# MemoryExpansion.net
KiCad netlist of a schematic drawn in EAGLE
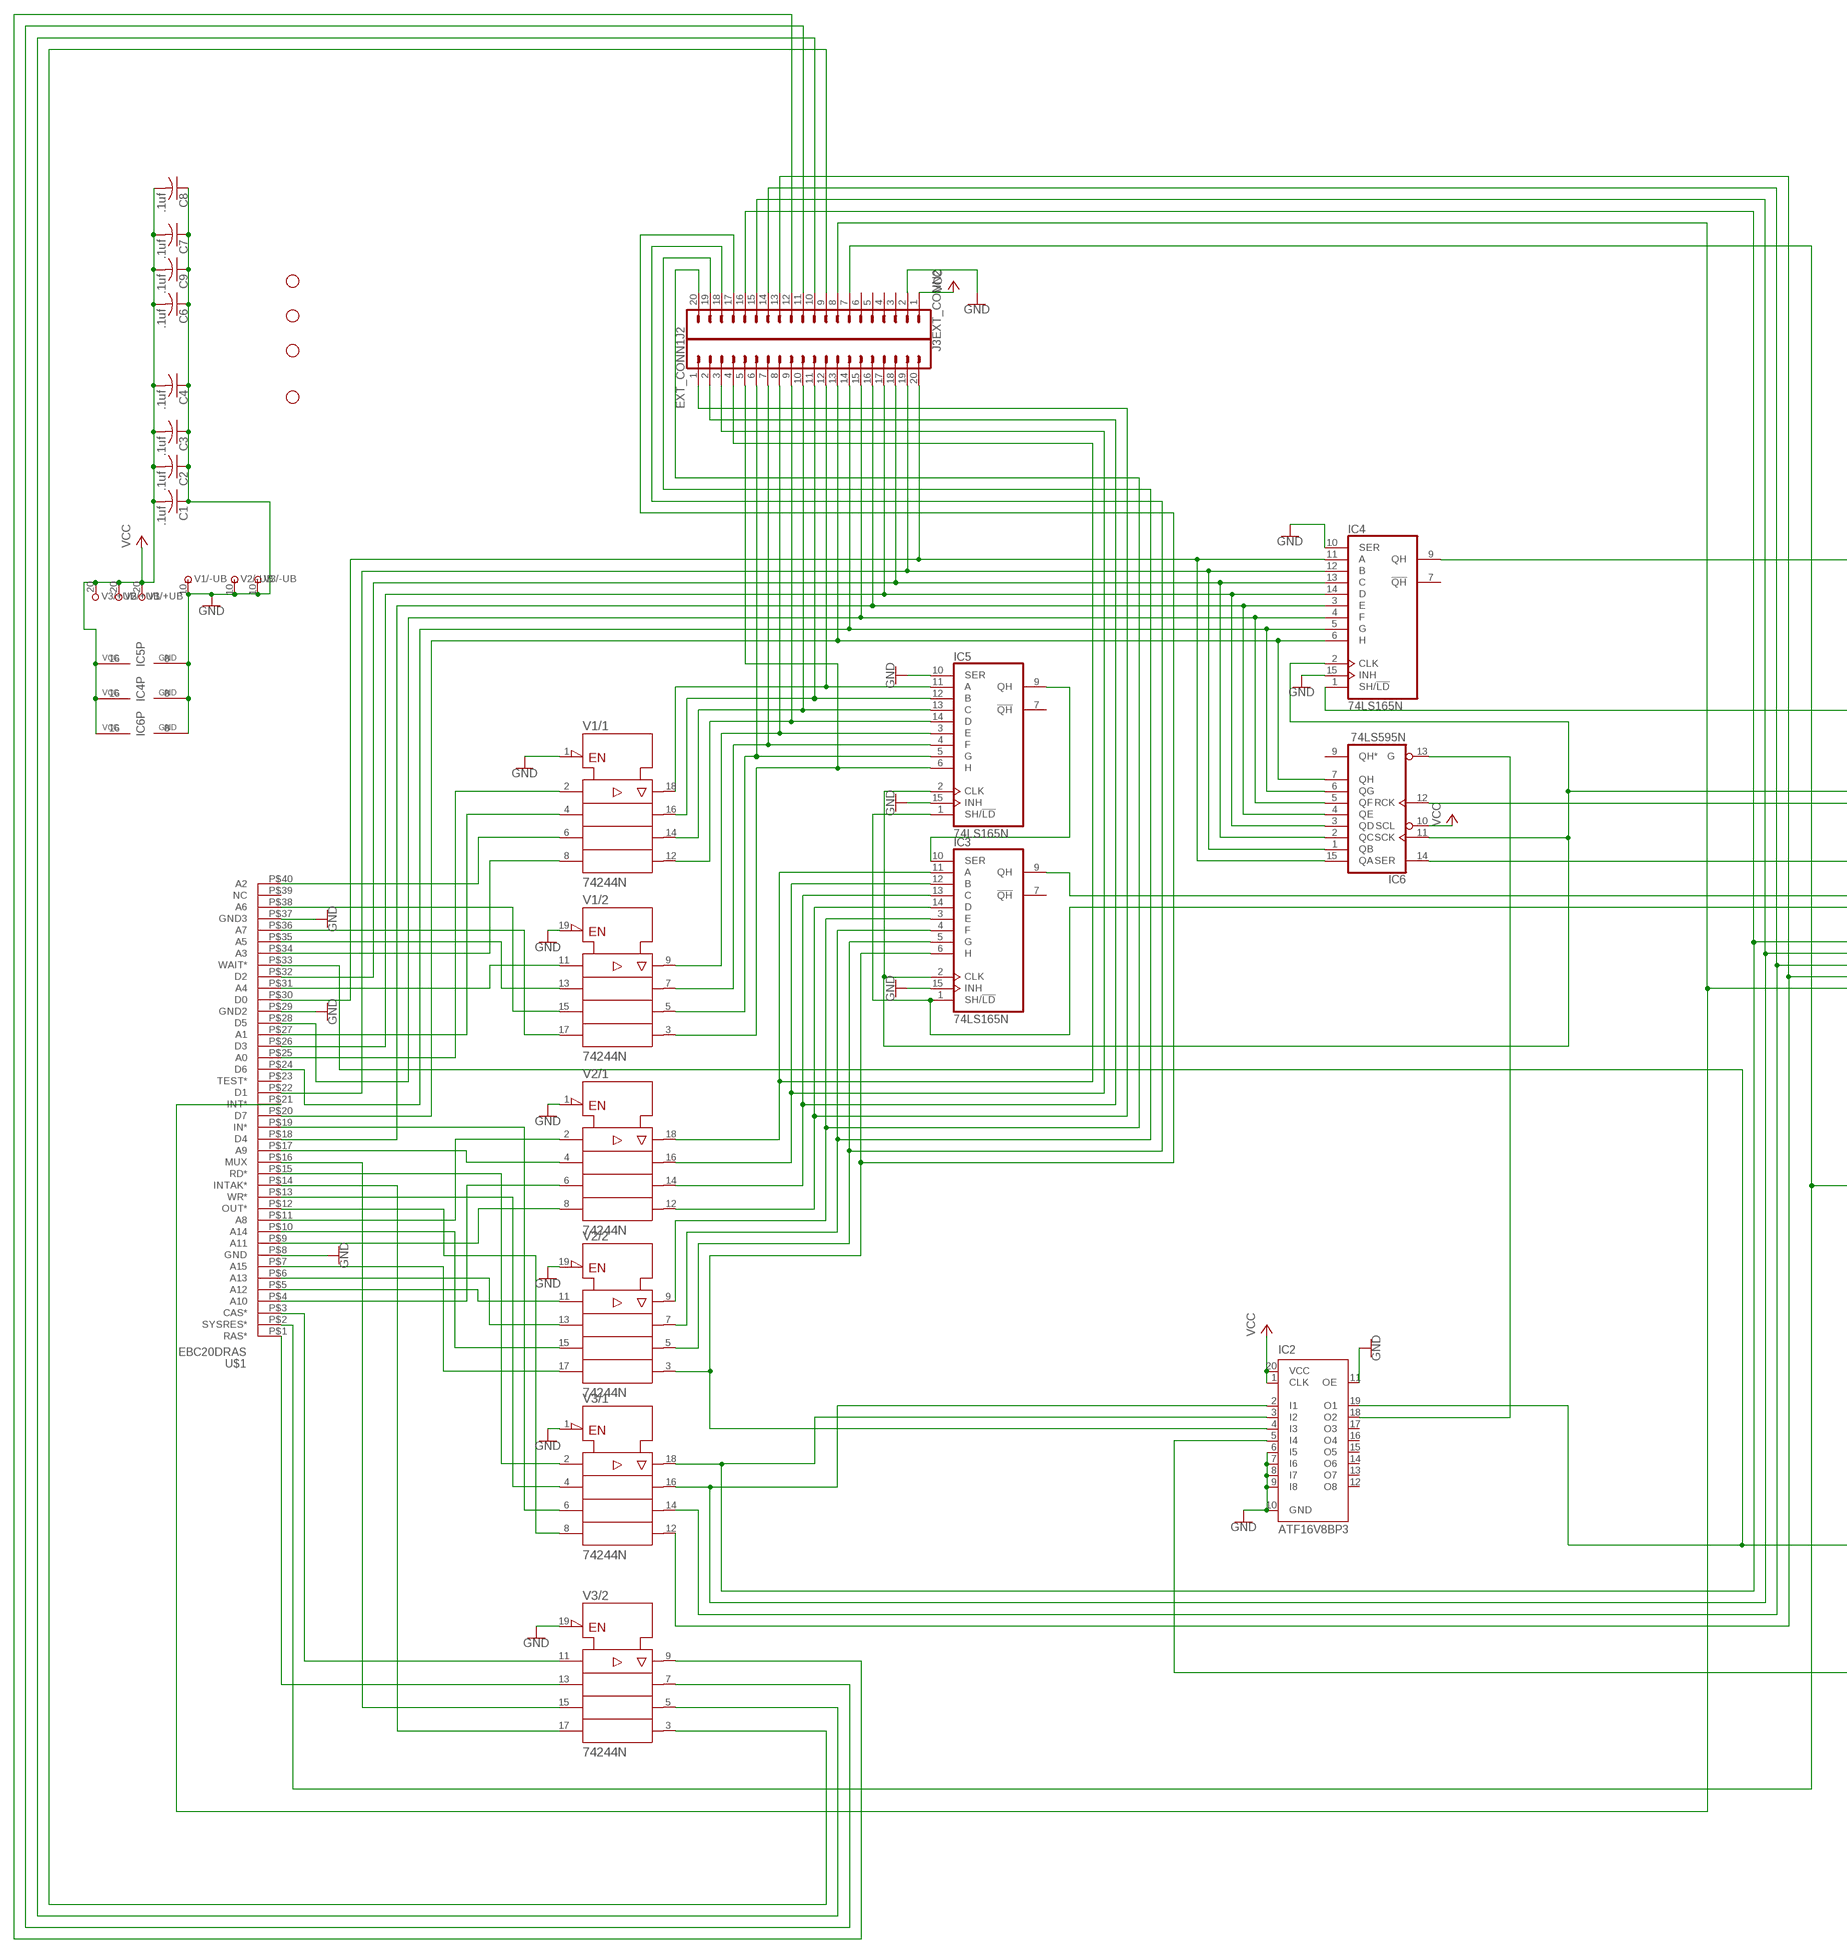
[diagram p0: schematic, sheet 1, part 1 of 2]
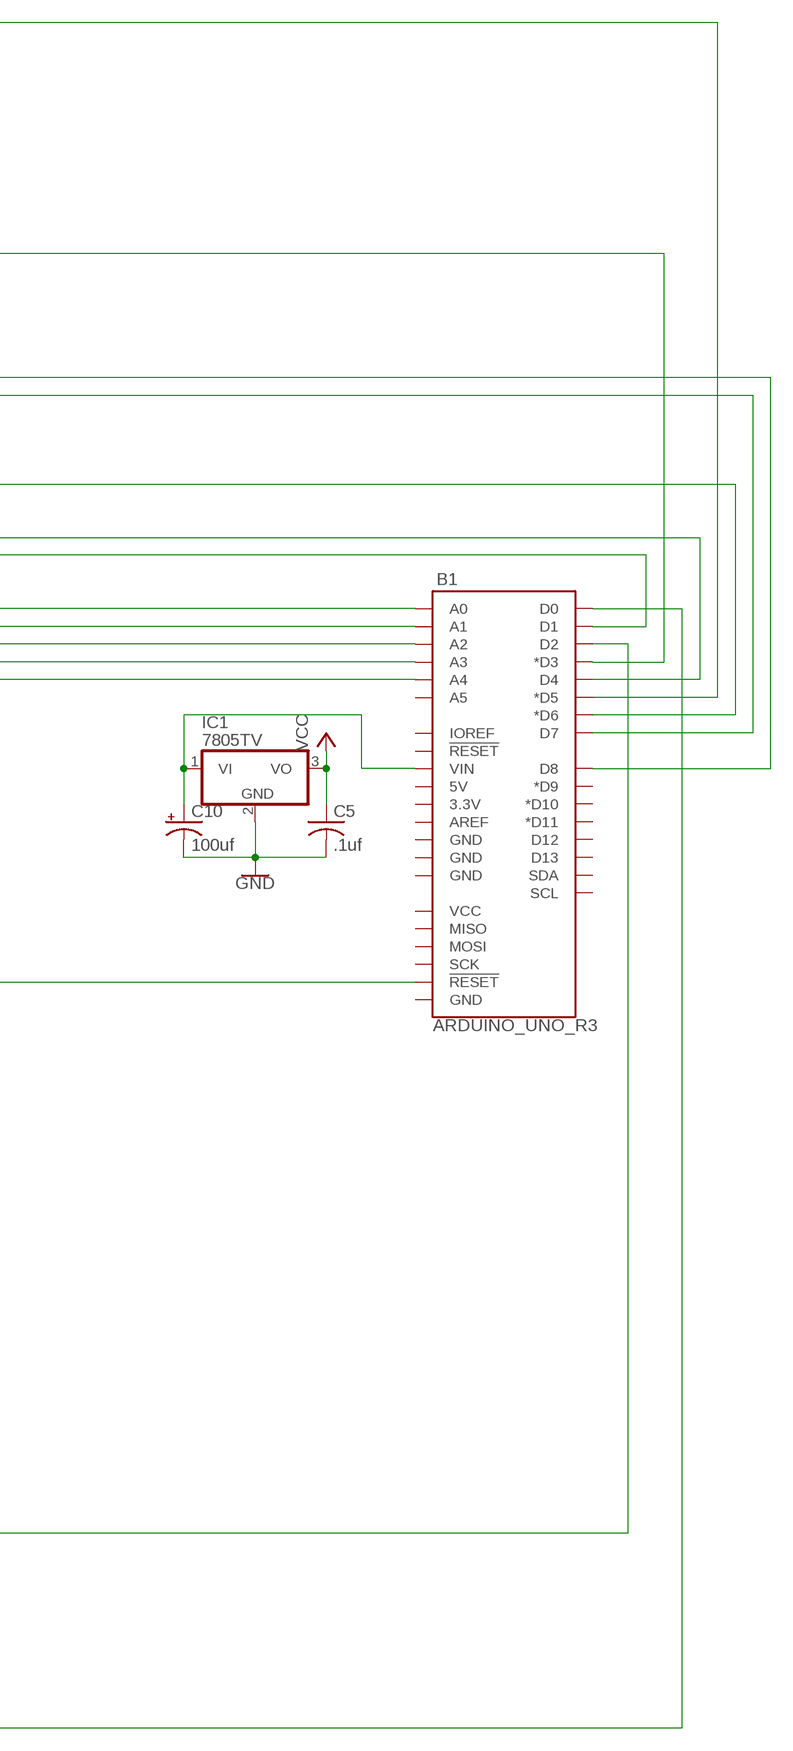
[diagram p1: schematic, sheet 1, part 2 of 2]

(export (version "E")
  (design (tool "Eeschema 10.0.6"))
  (components
    (comp (ref "B1")
      (value "ARDUINO_UNO_R3")
      (footprint "eagle-import:ARDUINO_R3")
      (libsource (lib "eagle-import") (part "ARDUINO_UNO_R3"))
    )
    (comp (ref "C1")
      (value ".1uf")
      (footprint "eagle-import:C025-024X044")
      (libsource (lib "eagle-import") (part "C-US025-024X044"))
    )
    (comp (ref "C2")
      (value ".1uf")
      (footprint "eagle-import:C025-024X044")
      (libsource (lib "eagle-import") (part "C-US025-024X044"))
    )
    (comp (ref "C3")
      (value ".1uf")
      (footprint "eagle-import:C025-024X044")
      (libsource (lib "eagle-import") (part "C-US025-024X044"))
    )
    (comp (ref "C4")
      (value ".1uf")
      (footprint "eagle-import:C025-024X044")
      (libsource (lib "eagle-import") (part "C-US025-024X044"))
    )
    (comp (ref "C5")
      (value ".1uf")
      (footprint "eagle-import:C025-024X044")
      (libsource (lib "eagle-import") (part "C-US025-024X044"))
    )
    (comp (ref "C6")
      (value ".1uf")
      (footprint "eagle-import:C025-024X044")
      (libsource (lib "eagle-import") (part "C-US025-024X044"))
    )
    (comp (ref "C7")
      (value ".1uf")
      (footprint "eagle-import:C025-024X044")
      (libsource (lib "eagle-import") (part "C-US025-024X044"))
    )
    (comp (ref "C8")
      (value ".1uf")
      (footprint "eagle-import:C025-024X044")
      (libsource (lib "eagle-import") (part "C-US025-024X044"))
    )
    (comp (ref "C9")
      (value ".1uf")
      (footprint "eagle-import:C025-024X044")
      (libsource (lib "eagle-import") (part "C-US025-024X044"))
    )
    (comp (ref "C10")
      (value "100uf")
      (footprint "eagle-import:E2-5")
      (libsource (lib "eagle-import") (part "CPOL-USE2-5"))
    )
    (comp (ref "H1")
      (value "STAND-OFF")
      (footprint "eagle-import:STAND-OFF")
      (libsource (lib "eagle-import") (part "STAND-OFF"))
    )
    (comp (ref "H2")
      (value "STAND-OFF")
      (footprint "eagle-import:STAND-OFF")
      (libsource (lib "eagle-import") (part "STAND-OFF"))
    )
    (comp (ref "H3")
      (value "STAND-OFF")
      (footprint "eagle-import:STAND-OFF")
      (libsource (lib "eagle-import") (part "STAND-OFF"))
    )
    (comp (ref "H4")
      (value "STAND-OFF")
      (footprint "eagle-import:STAND-OFF")
      (libsource (lib "eagle-import") (part "STAND-OFF"))
    )
    (comp (ref "IC1")
      (value "7805TV")
      (footprint "eagle-import:TO220V")
      (libsource (lib "eagle-import") (part "78TV05"))
    )
    (comp (ref "IC2")
      (value "ATF16V8BP3")
      (footprint "eagle-import:DIL20")
      (fields (field (name "MPN") "ATF16V8CZ-15PU"))
      (libsource (lib "eagle-import") (part "ATF16V8BP3"))
    )
    (comp (ref "IC3")
      (value "74LS165N")
      (footprint "eagle-import:DIL16")
      (libsource (lib "eagle-import") (part "74165NLS"))
    )
    (comp (ref "IC4")
      (value "74LS165N")
      (footprint "eagle-import:DIL16")
      (libsource (lib "eagle-import") (part "74165NLS"))
    )
    (comp (ref "IC5")
      (value "74LS165N")
      (footprint "eagle-import:DIL16")
      (libsource (lib "eagle-import") (part "74165NLS"))
    )
    (comp (ref "IC6")
      (value "74LS595N")
      (footprint "eagle-import:DIL16")
      (libsource (lib "eagle-import") (part "74595NLS"))
    )
    (comp (ref "J2")
      (value "EXT_CONN2")
      (footprint "eagle-import:1X20")
      (libsource (lib "eagle-import") (part "CONN_20"))
    )
    (comp (ref "J3")
      (value "EXT_CONN1")
      (footprint "eagle-import:1X20")
      (libsource (lib "eagle-import") (part "CONN_20"))
    )
    (comp (ref "U$1")
      (value "EBC20DRAS")
      (footprint "eagle-import:EBC20DRAS")
      (libsource (lib "eagle-import") (part "EBC20DRAS"))
    )
    (comp (ref "V1")
      (value "74244N")
      (footprint "eagle-import:DIL20")
      (libsource (lib "eagle-import") (part "74244N"))
    )
    (comp (ref "V2")
      (value "74244N")
      (footprint "eagle-import:DIL20")
      (libsource (lib "eagle-import") (part "74244N"))
    )
    (comp (ref "V3")
      (value "74244N")
      (footprint "eagle-import:DIL20")
      (libsource (lib "eagle-import") (part "74244N"))
    )
  )
  (nets
    (net (code "1") (name "GND") (class "Default")
      (node (ref "C1") (pin "1") (pinfunction "1_1") (pintype "passive"))
      (node (ref "C10") (pin "-") (pinfunction "-_-") (pintype "passive"))
      (node (ref "C2") (pin "1") (pinfunction "1_1") (pintype "passive"))
      (node (ref "C3") (pin "1") (pinfunction "1_1") (pintype "passive"))
      (node (ref "C4") (pin "1") (pinfunction "1_1") (pintype "passive"))
      (node (ref "C5") (pin "2") (pinfunction "2_2") (pintype "passive"))
      (node (ref "C6") (pin "1") (pinfunction "1_1") (pintype "passive"))
      (node (ref "C7") (pin "1") (pinfunction "1_1") (pintype "passive"))
      (node (ref "C8") (pin "1") (pinfunction "1_1") (pintype "passive"))
      (node (ref "C9") (pin "1") (pinfunction "1_1") (pintype "passive"))
      (node (ref "IC1") (pin "2") (pinfunction "GND_2") (pintype "passive"))
      (node (ref "IC2") (pin "10") (pinfunction "GND_10") (pintype "power_in"))
      (node (ref "IC2") (pin "11") (pinfunction "OE_11") (pintype "input"))
      (node (ref "IC2") (pin "6") (pinfunction "I5_6") (pintype "input"))
      (node (ref "IC2") (pin "7") (pinfunction "I6_7") (pintype "input"))
      (node (ref "IC2") (pin "8") (pinfunction "I7_8") (pintype "input"))
      (node (ref "IC2") (pin "9") (pinfunction "I8_9") (pintype "input"))
      (node (ref "IC3") (pin "15") (pinfunction "INH_15") (pintype "input"))
      (node (ref "IC4") (pin "10") (pinfunction "SER_10") (pintype "input"))
      (node (ref "IC4") (pin "15") (pinfunction "INH_15") (pintype "input"))
      (node (ref "IC4") (pin "8") (pinfunction "GND_8") (pintype "power_in"))
      (node (ref "IC5") (pin "10") (pinfunction "SER_10") (pintype "input"))
      (node (ref "IC5") (pin "15") (pinfunction "INH_15") (pintype "input"))
      (node (ref "IC5") (pin "8") (pinfunction "GND_8") (pintype "power_in"))
      (node (ref "IC6") (pin "8") (pinfunction "GND_8") (pintype "power_in"))
      (node (ref "J2") (pin "2") (pinfunction "2_2") (pintype "passive"))
      (node (ref "U$1") (pin "P$29") (pinfunction "GND2_P$29") (pintype "bidirectional"))
      (node (ref "U$1") (pin "P$37") (pinfunction "GND3_P$37") (pintype "bidirectional"))
      (node (ref "U$1") (pin "P$8") (pinfunction "GND_P$8") (pintype "bidirectional"))
      (node (ref "V1") (pin "1") (pinfunction "~{G}_1") (pintype "input"))
      (node (ref "V1") (pin "10") (pinfunction "-UB_10") (pintype "power_in"))
      (node (ref "V1") (pin "19") (pinfunction "~{G}_19") (pintype "input"))
      (node (ref "V2") (pin "1") (pinfunction "~{G}_1") (pintype "input"))
      (node (ref "V2") (pin "10") (pinfunction "-UB_10") (pintype "power_in"))
      (node (ref "V2") (pin "19") (pinfunction "~{G}_19") (pintype "input"))
      (node (ref "V3") (pin "1") (pinfunction "~{G}_1") (pintype "input"))
      (node (ref "V3") (pin "10") (pinfunction "-UB_10") (pintype "power_in"))
      (node (ref "V3") (pin "19") (pinfunction "~{G}_19") (pintype "input"))
    )
    (net (code "2") (name "Net-(B1-*D3)") (class "Default")
      (node (ref "B1") (pin "D3") (pinfunction "*D3_D3") (pintype "bidirectional"))
      (node (ref "IC4") (pin "1") (pinfunction "SH/~{LD}_1") (pintype "input"))
    )
    (net (code "3") (name "Net-(B1-*D5)") (class "Default")
      (node (ref "B1") (pin "D5") (pinfunction "*D5_D5") (pintype "bidirectional"))
      (node (ref "IC4") (pin "9") (pinfunction "QH_9") (pintype "output"))
    )
    (net (code "4") (name "Net-(B1-*D6)") (class "Default")
      (node (ref "B1") (pin "D6") (pinfunction "*D6_D6") (pintype "bidirectional"))
      (node (ref "IC6") (pin "14") (pinfunction "SER_14") (pintype "input"))
    )
    (net (code "5") (name "Net-(IC1-VI)") (class "Default")
      (node (ref "B1") (pin "VIN") (pinfunction "VIN_VIN") (pintype "bidirectional"))
      (node (ref "C10") (pin "+") (pinfunction "+_+") (pintype "passive"))
      (node (ref "IC1") (pin "1") (pinfunction "VI_1") (pintype "input"))
    )
    (net (code "6") (name "Net-(IC2-I1)") (class "Default")
      (node (ref "B1") (pin "A1") (pinfunction "A1_A1") (pintype "bidirectional"))
      (node (ref "IC2") (pin "2") (pinfunction "I1_2") (pintype "input"))
      (node (ref "J2") (pin "15") (pinfunction "15_15") (pintype "passive"))
      (node (ref "V3") (pin "16") (pinfunction "Y2_16") (pintype "tri_state"))
    )
    (net (code "7") (name "Net-(IC2-I2)") (class "Default")
      (node (ref "B1") (pin "A0") (pinfunction "A0_A0") (pintype "bidirectional"))
      (node (ref "IC2") (pin "3") (pinfunction "I2_3") (pintype "input"))
      (node (ref "J2") (pin "16") (pinfunction "16_16") (pintype "passive"))
      (node (ref "V3") (pin "18") (pinfunction "Y1_18") (pintype "tri_state"))
    )
    (net (code "8") (name "Net-(IC2-I3)") (class "Default")
      (node (ref "IC2") (pin "4") (pinfunction "I3_4") (pintype "input"))
      (node (ref "IC3") (pin "6") (pinfunction "H_6") (pintype "input"))
      (node (ref "J2") (pin "17") (pinfunction "17_17") (pintype "passive"))
      (node (ref "V2") (pin "3") (pinfunction "Y4_3") (pintype "tri_state"))
    )
    (net (code "9") (name "Net-(IC2-I4)") (class "Default")
      (node (ref "B1") (pin "D0") (pinfunction "D0_D0") (pintype "bidirectional"))
      (node (ref "IC2") (pin "5") (pinfunction "I4_5") (pintype "input"))
    )
    (net (code "10") (name "Net-(IC2-O1)") (class "Default")
      (node (ref "B1") (pin "D2") (pinfunction "D2_D2") (pintype "bidirectional"))
      (node (ref "IC2") (pin "19") (pinfunction "O1_19") (pintype "output"))
      (node (ref "U$1") (pin "P$33") (pinfunction "WAIT*_P$33") (pintype "bidirectional"))
    )
    (net (code "11") (name "Net-(IC2-O2)") (class "Default")
      (node (ref "IC2") (pin "18") (pinfunction "O2_18") (pintype "output"))
      (node (ref "IC6") (pin "13") (pinfunction "G_13") (pintype "input"))
    )
    (net (code "12") (name "Net-(IC3A-A)") (class "Default")
      (node (ref "IC3") (pin "11") (pinfunction "A_11") (pintype "input"))
      (node (ref "J3") (pin "4") (pinfunction "4_4") (pintype "passive"))
      (node (ref "V2") (pin "18") (pinfunction "Y1_18") (pintype "tri_state"))
    )
    (net (code "13") (name "Net-(IC3A-B)") (class "Default")
      (node (ref "IC3") (pin "12") (pinfunction "B_12") (pintype "input"))
      (node (ref "J3") (pin "3") (pinfunction "3_3") (pintype "passive"))
      (node (ref "V2") (pin "16") (pinfunction "Y2_16") (pintype "tri_state"))
    )
    (net (code "14") (name "Net-(IC3A-C)") (class "Default")
      (node (ref "IC3") (pin "13") (pinfunction "C_13") (pintype "input"))
      (node (ref "J3") (pin "2") (pinfunction "2_2") (pintype "passive"))
      (node (ref "V2") (pin "14") (pinfunction "Y3_14") (pintype "tri_state"))
    )
    (net (code "15") (name "Net-(IC3A-CLK)") (class "Default")
      (node (ref "B1") (pin "D8") (pinfunction "D8_D8") (pintype "bidirectional"))
      (node (ref "IC3") (pin "2") (pinfunction "CLK_2") (pintype "input"))
      (node (ref "IC4") (pin "2") (pinfunction "CLK_2") (pintype "input"))
      (node (ref "IC5") (pin "2") (pinfunction "CLK_2") (pintype "input"))
      (node (ref "IC6") (pin "11") (pinfunction "SCK_11") (pintype "input"))
    )
    (net (code "16") (name "Net-(IC3A-D)") (class "Default")
      (node (ref "IC3") (pin "14") (pinfunction "D_14") (pintype "input"))
      (node (ref "J3") (pin "1") (pinfunction "1_1") (pintype "passive"))
      (node (ref "V2") (pin "12") (pinfunction "Y4_12") (pintype "tri_state"))
    )
    (net (code "17") (name "Net-(IC3A-E)") (class "Default")
      (node (ref "IC3") (pin "3") (pinfunction "E_3") (pintype "input"))
      (node (ref "J2") (pin "20") (pinfunction "20_20") (pintype "passive"))
      (node (ref "V2") (pin "9") (pinfunction "Y1_9") (pintype "tri_state"))
    )
    (net (code "18") (name "Net-(IC3A-F)") (class "Default")
      (node (ref "IC3") (pin "4") (pinfunction "F_4") (pintype "input"))
      (node (ref "J2") (pin "19") (pinfunction "19_19") (pintype "passive"))
      (node (ref "V2") (pin "7") (pinfunction "Y2_7") (pintype "tri_state"))
    )
    (net (code "19") (name "Net-(IC3A-G)") (class "Default")
      (node (ref "IC3") (pin "5") (pinfunction "G_5") (pintype "input"))
      (node (ref "J2") (pin "18") (pinfunction "18_18") (pintype "passive"))
      (node (ref "V2") (pin "5") (pinfunction "Y3_5") (pintype "tri_state"))
    )
    (net (code "20") (name "Net-(IC3A-QH)") (class "Default")
      (node (ref "B1") (pin "D4") (pinfunction "D4_D4") (pintype "bidirectional"))
      (node (ref "IC3") (pin "9") (pinfunction "QH_9") (pintype "output"))
    )
    (net (code "21") (name "Net-(IC3A-SER)") (class "Default")
      (node (ref "IC3") (pin "10") (pinfunction "SER_10") (pintype "input"))
      (node (ref "IC5") (pin "9") (pinfunction "QH_9") (pintype "output"))
    )
    (net (code "22") (name "Net-(IC3A-SH{slash}~{LD})") (class "Default")
      (node (ref "B1") (pin "D1") (pinfunction "D1_D1") (pintype "bidirectional"))
      (node (ref "IC3") (pin "1") (pinfunction "SH/~{LD}_1") (pintype "input"))
      (node (ref "IC5") (pin "1") (pinfunction "SH/~{LD}_1") (pintype "input"))
    )
    (net (code "23") (name "Net-(IC4A-A)") (class "Default")
      (node (ref "IC4") (pin "11") (pinfunction "A_11") (pintype "input"))
      (node (ref "IC6") (pin "15") (pinfunction "QA_15") (pintype "tri_state"))
      (node (ref "J3") (pin "20") (pinfunction "20_20") (pintype "passive"))
      (node (ref "U$1") (pin "P$30") (pinfunction "D0_P$30") (pintype "bidirectional"))
    )
    (net (code "24") (name "Net-(IC4A-B)") (class "Default")
      (node (ref "IC4") (pin "12") (pinfunction "B_12") (pintype "input"))
      (node (ref "IC6") (pin "1") (pinfunction "QB_1") (pintype "tri_state"))
      (node (ref "J3") (pin "19") (pinfunction "19_19") (pintype "passive"))
      (node (ref "U$1") (pin "P$22") (pinfunction "D1_P$22") (pintype "bidirectional"))
    )
    (net (code "25") (name "Net-(IC4A-C)") (class "Default")
      (node (ref "IC4") (pin "13") (pinfunction "C_13") (pintype "input"))
      (node (ref "IC6") (pin "2") (pinfunction "QC_2") (pintype "tri_state"))
      (node (ref "J3") (pin "18") (pinfunction "18_18") (pintype "passive"))
      (node (ref "U$1") (pin "P$32") (pinfunction "D2_P$32") (pintype "bidirectional"))
    )
    (net (code "26") (name "Net-(IC4A-D)") (class "Default")
      (node (ref "IC4") (pin "14") (pinfunction "D_14") (pintype "input"))
      (node (ref "IC6") (pin "3") (pinfunction "QD_3") (pintype "tri_state"))
      (node (ref "J3") (pin "17") (pinfunction "17_17") (pintype "passive"))
      (node (ref "U$1") (pin "P$26") (pinfunction "D3_P$26") (pintype "bidirectional"))
    )
    (net (code "27") (name "Net-(IC4A-E)") (class "Default")
      (node (ref "IC4") (pin "3") (pinfunction "E_3") (pintype "input"))
      (node (ref "IC6") (pin "4") (pinfunction "QE_4") (pintype "tri_state"))
      (node (ref "J3") (pin "16") (pinfunction "16_16") (pintype "passive"))
      (node (ref "U$1") (pin "P$18") (pinfunction "D4_P$18") (pintype "bidirectional"))
    )
    (net (code "28") (name "Net-(IC4A-F)") (class "Default")
      (node (ref "IC4") (pin "4") (pinfunction "F_4") (pintype "input"))
      (node (ref "IC6") (pin "5") (pinfunction "QF_5") (pintype "tri_state"))
      (node (ref "J3") (pin "15") (pinfunction "15_15") (pintype "passive"))
      (node (ref "U$1") (pin "P$28") (pinfunction "D5_P$28") (pintype "bidirectional"))
    )
    (net (code "29") (name "Net-(IC4A-G)") (class "Default")
      (node (ref "IC4") (pin "5") (pinfunction "G_5") (pintype "input"))
      (node (ref "IC6") (pin "6") (pinfunction "QG_6") (pintype "tri_state"))
      (node (ref "J3") (pin "14") (pinfunction "14_14") (pintype "passive"))
      (node (ref "U$1") (pin "P$24") (pinfunction "D6_P$24") (pintype "bidirectional"))
    )
    (net (code "30") (name "Net-(IC4A-H)") (class "Default")
      (node (ref "IC4") (pin "6") (pinfunction "H_6") (pintype "input"))
      (node (ref "IC6") (pin "7") (pinfunction "QH_7") (pintype "tri_state"))
      (node (ref "J3") (pin "13") (pinfunction "13_13") (pintype "passive"))
      (node (ref "U$1") (pin "P$20") (pinfunction "D7_P$20") (pintype "bidirectional"))
    )
    (net (code "31") (name "Net-(IC5A-A)") (class "Default")
      (node (ref "IC5") (pin "11") (pinfunction "A_11") (pintype "input"))
      (node (ref "J3") (pin "12") (pinfunction "12_12") (pintype "passive"))
      (node (ref "V1") (pin "18") (pinfunction "Y1_18") (pintype "tri_state"))
    )
    (net (code "32") (name "Net-(IC5A-B)") (class "Default")
      (node (ref "IC5") (pin "12") (pinfunction "B_12") (pintype "input"))
      (node (ref "J3") (pin "11") (pinfunction "11_11") (pintype "passive"))
      (node (ref "V1") (pin "16") (pinfunction "Y2_16") (pintype "tri_state"))
    )
    (net (code "33") (name "Net-(IC5A-C)") (class "Default")
      (node (ref "IC5") (pin "13") (pinfunction "C_13") (pintype "input"))
      (node (ref "J3") (pin "10") (pinfunction "10_10") (pintype "passive"))
      (node (ref "V1") (pin "14") (pinfunction "Y3_14") (pintype "tri_state"))
    )
    (net (code "34") (name "Net-(IC5A-D)") (class "Default")
      (node (ref "IC5") (pin "14") (pinfunction "D_14") (pintype "input"))
      (node (ref "J3") (pin "9") (pinfunction "9_9") (pintype "passive"))
      (node (ref "V1") (pin "12") (pinfunction "Y4_12") (pintype "tri_state"))
    )
    (net (code "35") (name "Net-(IC5A-E)") (class "Default")
      (node (ref "IC5") (pin "3") (pinfunction "E_3") (pintype "input"))
      (node (ref "J3") (pin "8") (pinfunction "8_8") (pintype "passive"))
      (node (ref "V1") (pin "9") (pinfunction "Y1_9") (pintype "tri_state"))
    )
    (net (code "36") (name "Net-(IC5A-F)") (class "Default")
      (node (ref "IC5") (pin "4") (pinfunction "F_4") (pintype "input"))
      (node (ref "J3") (pin "7") (pinfunction "7_7") (pintype "passive"))
      (node (ref "V1") (pin "7") (pinfunction "Y2_7") (pintype "tri_state"))
    )
    (net (code "37") (name "Net-(IC5A-G)") (class "Default")
      (node (ref "IC5") (pin "5") (pinfunction "G_5") (pintype "input"))
      (node (ref "J3") (pin "6") (pinfunction "6_6") (pintype "passive"))
      (node (ref "V1") (pin "5") (pinfunction "Y3_5") (pintype "tri_state"))
    )
    (net (code "38") (name "Net-(IC5A-H)") (class "Default")
      (node (ref "IC5") (pin "6") (pinfunction "H_6") (pintype "input"))
      (node (ref "J3") (pin "5") (pinfunction "5_5") (pintype "passive"))
      (node (ref "V1") (pin "3") (pinfunction "Y4_3") (pintype "tri_state"))
    )
    (net (code "39") (name "Net-(IC6A-RCK)") (class "Default")
      (node (ref "B1") (pin "D7") (pinfunction "D7_D7") (pintype "bidirectional"))
      (node (ref "IC6") (pin "12") (pinfunction "RCK_12") (pintype "input"))
    )
    (net (code "40") (name "Net-(U$1-A0)") (class "Default")
      (node (ref "U$1") (pin "P$25") (pinfunction "A0_P$25") (pintype "bidirectional"))
      (node (ref "V1") (pin "2") (pinfunction "A1_2") (pintype "input"))
    )
    (net (code "41") (name "Net-(U$1-A1)") (class "Default")
      (node (ref "U$1") (pin "P$27") (pinfunction "A1_P$27") (pintype "bidirectional"))
      (node (ref "V1") (pin "4") (pinfunction "A2_4") (pintype "input"))
    )
    (net (code "42") (name "Net-(U$1-A2)") (class "Default")
      (node (ref "U$1") (pin "P$40") (pinfunction "A2_P$40") (pintype "bidirectional"))
      (node (ref "V1") (pin "6") (pinfunction "A3_6") (pintype "input"))
    )
    (net (code "43") (name "Net-(U$1-A3)") (class "Default")
      (node (ref "U$1") (pin "P$34") (pinfunction "A3_P$34") (pintype "bidirectional"))
      (node (ref "V1") (pin "8") (pinfunction "A4_8") (pintype "input"))
    )
    (net (code "44") (name "Net-(U$1-A4)") (class "Default")
      (node (ref "U$1") (pin "P$31") (pinfunction "A4_P$31") (pintype "bidirectional"))
      (node (ref "V1") (pin "11") (pinfunction "A1_11") (pintype "input"))
    )
    (net (code "45") (name "Net-(U$1-A5)") (class "Default")
      (node (ref "U$1") (pin "P$35") (pinfunction "A5_P$35") (pintype "bidirectional"))
      (node (ref "V1") (pin "13") (pinfunction "A2_13") (pintype "input"))
    )
    (net (code "46") (name "Net-(U$1-A6)") (class "Default")
      (node (ref "U$1") (pin "P$38") (pinfunction "A6_P$38") (pintype "bidirectional"))
      (node (ref "V1") (pin "15") (pinfunction "A3_15") (pintype "input"))
    )
    (net (code "47") (name "Net-(U$1-A7)") (class "Default")
      (node (ref "U$1") (pin "P$36") (pinfunction "A7_P$36") (pintype "bidirectional"))
      (node (ref "V1") (pin "17") (pinfunction "A4_17") (pintype "input"))
    )
    (net (code "48") (name "Net-(U$1-A8)") (class "Default")
      (node (ref "U$1") (pin "P$11") (pinfunction "A8_P$11") (pintype "bidirectional"))
      (node (ref "V2") (pin "2") (pinfunction "A1_2") (pintype "input"))
    )
    (net (code "49") (name "Net-(U$1-A9)") (class "Default")
      (node (ref "U$1") (pin "P$17") (pinfunction "A9_P$17") (pintype "bidirectional"))
      (node (ref "V2") (pin "4") (pinfunction "A2_4") (pintype "input"))
    )
    (net (code "50") (name "Net-(U$1-A10)") (class "Default")
      (node (ref "U$1") (pin "P$4") (pinfunction "A10_P$4") (pintype "bidirectional"))
      (node (ref "V2") (pin "6") (pinfunction "A3_6") (pintype "input"))
    )
    (net (code "51") (name "Net-(U$1-A11)") (class "Default")
      (node (ref "U$1") (pin "P$9") (pinfunction "A11_P$9") (pintype "bidirectional"))
      (node (ref "V2") (pin "8") (pinfunction "A4_8") (pintype "input"))
    )
    (net (code "52") (name "Net-(U$1-A12)") (class "Default")
      (node (ref "U$1") (pin "P$5") (pinfunction "A12_P$5") (pintype "bidirectional"))
      (node (ref "V2") (pin "11") (pinfunction "A1_11") (pintype "input"))
    )
    (net (code "53") (name "Net-(U$1-A13)") (class "Default")
      (node (ref "U$1") (pin "P$6") (pinfunction "A13_P$6") (pintype "bidirectional"))
      (node (ref "V2") (pin "13") (pinfunction "A2_13") (pintype "input"))
    )
    (net (code "54") (name "Net-(U$1-A14)") (class "Default")
      (node (ref "U$1") (pin "P$10") (pinfunction "A14_P$10") (pintype "bidirectional"))
      (node (ref "V2") (pin "15") (pinfunction "A3_15") (pintype "input"))
    )
    (net (code "55") (name "Net-(U$1-A15)") (class "Default")
      (node (ref "U$1") (pin "P$7") (pinfunction "A15_P$7") (pintype "bidirectional"))
      (node (ref "V2") (pin "17") (pinfunction "A4_17") (pintype "input"))
    )
    (net (code "56") (name "Net-(U$1-CAS*)") (class "Default")
      (node (ref "U$1") (pin "P$3") (pinfunction "CAS*_P$3") (pintype "bidirectional"))
      (node (ref "V3") (pin "11") (pinfunction "A1_11") (pintype "input"))
    )
    (net (code "57") (name "Net-(U$1-IN*)") (class "Default")
      (node (ref "U$1") (pin "P$19") (pinfunction "IN*_P$19") (pintype "bidirectional"))
      (node (ref "V3") (pin "6") (pinfunction "A3_6") (pintype "input"))
    )
    (net (code "58") (name "Net-(U$1-INT*)") (class "Default")
      (node (ref "B1") (pin "A4") (pinfunction "A4_A4") (pintype "bidirectional"))
      (node (ref "J2") (pin "8") (pinfunction "8_8") (pintype "passive"))
      (node (ref "U$1") (pin "P$21") (pinfunction "INT*_P$21") (pintype "bidirectional"))
    )
    (net (code "59") (name "Net-(U$1-INTAK*)") (class "Default")
      (node (ref "U$1") (pin "P$14") (pinfunction "INTAK*_P$14") (pintype "bidirectional"))
      (node (ref "V3") (pin "17") (pinfunction "A4_17") (pintype "input"))
    )
    (net (code "60") (name "Net-(U$1-MUX)") (class "Default")
      (node (ref "U$1") (pin "P$16") (pinfunction "MUX_P$16") (pintype "bidirectional"))
      (node (ref "V3") (pin "15") (pinfunction "A3_15") (pintype "input"))
    )
    (net (code "61") (name "Net-(U$1-OUT*)") (class "Default")
      (node (ref "U$1") (pin "P$12") (pinfunction "OUT*_P$12") (pintype "bidirectional"))
      (node (ref "V3") (pin "8") (pinfunction "A4_8") (pintype "input"))
    )
    (net (code "62") (name "Net-(U$1-RAS*)") (class "Default")
      (node (ref "U$1") (pin "P$1") (pinfunction "RAS*_P$1") (pintype "bidirectional"))
      (node (ref "V3") (pin "13") (pinfunction "A2_13") (pintype "input"))
    )
    (net (code "63") (name "Net-(U$1-RD*)") (class "Default")
      (node (ref "U$1") (pin "P$15") (pinfunction "RD*_P$15") (pintype "bidirectional"))
      (node (ref "V3") (pin "2") (pinfunction "A1_2") (pintype "input"))
    )
    (net (code "64") (name "Net-(U$1-SYSRES*)") (class "Default")
      (node (ref "B1") (pin "RESET@2") (pinfunction "~{RESET}_RESET@2") (pintype "bidirectional"))
      (node (ref "J2") (pin "7") (pinfunction "7_7") (pintype "passive"))
      (node (ref "U$1") (pin "P$2") (pinfunction "SYSRES*_P$2") (pintype "bidirectional"))
    )
    (net (code "65") (name "Net-(U$1-WR*)") (class "Default")
      (node (ref "U$1") (pin "P$13") (pinfunction "WR*_P$13") (pintype "bidirectional"))
      (node (ref "V3") (pin "4") (pinfunction "A2_4") (pintype "input"))
    )
    (net (code "66") (name "Net-(V3C-Y3)") (class "Default")
      (node (ref "B1") (pin "A2") (pinfunction "A2_A2") (pintype "bidirectional"))
      (node (ref "J2") (pin "14") (pinfunction "14_14") (pintype "passive"))
      (node (ref "V3") (pin "14") (pinfunction "Y3_14") (pintype "tri_state"))
    )
    (net (code "67") (name "Net-(V3C-Y4)") (class "Default")
      (node (ref "B1") (pin "A3") (pinfunction "A3_A3") (pintype "bidirectional"))
      (node (ref "J2") (pin "13") (pinfunction "13_13") (pintype "passive"))
      (node (ref "V3") (pin "12") (pinfunction "Y4_12") (pintype "tri_state"))
    )
    (net (code "68") (name "Net-(V3D-Y1)") (class "Default")
      (node (ref "J2") (pin "12") (pinfunction "12_12") (pintype "passive"))
      (node (ref "V3") (pin "9") (pinfunction "Y1_9") (pintype "tri_state"))
    )
    (net (code "69") (name "Net-(V3D-Y2)") (class "Default")
      (node (ref "J2") (pin "11") (pinfunction "11_11") (pintype "passive"))
      (node (ref "V3") (pin "7") (pinfunction "Y2_7") (pintype "tri_state"))
    )
    (net (code "70") (name "Net-(V3D-Y3)") (class "Default")
      (node (ref "J2") (pin "10") (pinfunction "10_10") (pintype "passive"))
      (node (ref "V3") (pin "5") (pinfunction "Y3_5") (pintype "tri_state"))
    )
    (net (code "71") (name "Net-(V3D-Y4)") (class "Default")
      (node (ref "J2") (pin "9") (pinfunction "9_9") (pintype "passive"))
      (node (ref "V3") (pin "3") (pinfunction "Y4_3") (pintype "tri_state"))
    )
    (net (code "72") (name "VCC") (class "Default")
      (node (ref "C1") (pin "2") (pinfunction "2_2") (pintype "passive"))
      (node (ref "C2") (pin "2") (pinfunction "2_2") (pintype "passive"))
      (node (ref "C3") (pin "2") (pinfunction "2_2") (pintype "passive"))
      (node (ref "C4") (pin "2") (pinfunction "2_2") (pintype "passive"))
      (node (ref "C5") (pin "1") (pinfunction "1_1") (pintype "passive"))
      (node (ref "C6") (pin "2") (pinfunction "2_2") (pintype "passive"))
      (node (ref "C7") (pin "2") (pinfunction "2_2") (pintype "passive"))
      (node (ref "C8") (pin "2") (pinfunction "2_2") (pintype "passive"))
      (node (ref "C9") (pin "2") (pinfunction "2_2") (pintype "passive"))
      (node (ref "IC1") (pin "3") (pinfunction "VO_3") (pintype "passive"))
      (node (ref "IC2") (pin "1") (pinfunction "CLK_1") (pintype "input"))
      (node (ref "IC2") (pin "20") (pinfunction "VCC_20") (pintype "power_in"))
      (node (ref "IC4") (pin "16") (pinfunction "VCC_16") (pintype "power_in"))
      (node (ref "IC5") (pin "16") (pinfunction "VCC_16") (pintype "power_in"))
      (node (ref "IC6") (pin "10") (pinfunction "SCL_10") (pintype "input"))
      (node (ref "IC6") (pin "16") (pinfunction "VCC_16") (pintype "power_in"))
      (node (ref "J2") (pin "1") (pinfunction "1_1") (pintype "passive"))
      (node (ref "V1") (pin "20") (pinfunction "+UB_20") (pintype "power_in"))
      (node (ref "V2") (pin "20") (pinfunction "+UB_20") (pintype "power_in"))
      (node (ref "V3") (pin "20") (pinfunction "+UB_20") (pintype "power_in"))
    )
    (net (code "73") (name "unconnected-(B1-*D9-PadD9)") (class "Default")
      (node (ref "B1") (pin "D9") (pinfunction "*D9_D9") (pintype "bidirectional"))
    )
    (net (code "74") (name "unconnected-(B1-*D10-PadD10)") (class "Default")
      (node (ref "B1") (pin "D10") (pinfunction "*D10_D10") (pintype "bidirectional"))
    )
    (net (code "75") (name "unconnected-(B1-*D11-PadD11)") (class "Default")
      (node (ref "B1") (pin "D11") (pinfunction "*D11_D11") (pintype "bidirectional"))
    )
    (net (code "76") (name "unconnected-(B1-GND-PadGND@1)") (class "Default")
      (node (ref "B1") (pin "GND@1") (pinfunction "GND_GND@1") (pintype "bidirectional"))
    )
    (net (code "77") (name "unconnected-(B1-GND-PadGND@2)") (class "Default")
      (node (ref "B1") (pin "GND@2") (pinfunction "GND_GND@2") (pintype "bidirectional"))
    )
    (net (code "78") (name "unconnected-(B1-GND-PadGND@3)") (class "Default")
      (node (ref "B1") (pin "GND@3") (pinfunction "GND_GND@3") (pintype "bidirectional"))
    )
    (net (code "79") (name "unconnected-(B1-GND-PadGND@4)") (class "Default")
      (node (ref "B1") (pin "GND@4") (pinfunction "GND_GND@4") (pintype "bidirectional"))
    )
    (net (code "80") (name "unconnected-(B1-Pad3.3V)") (class "Default")
      (node (ref "B1") (pin "3.3V") (pinfunction "3.3V_3.3V") (pintype "bidirectional"))
    )
    (net (code "81") (name "unconnected-(B1-Pad5V)") (class "Default")
      (node (ref "B1") (pin "5V") (pinfunction "5V_5V") (pintype "bidirectional"))
    )
    (net (code "82") (name "unconnected-(B1-PadA5)") (class "Default")
      (node (ref "B1") (pin "A5") (pinfunction "A5_A5") (pintype "bidirectional"))
    )
    (net (code "83") (name "unconnected-(B1-PadAREF)") (class "Default")
      (node (ref "B1") (pin "AREF") (pinfunction "AREF_AREF") (pintype "bidirectional"))
    )
    (net (code "84") (name "unconnected-(B1-PadD12)") (class "Default")
      (node (ref "B1") (pin "D12") (pinfunction "D12_D12") (pintype "bidirectional"))
    )
    (net (code "85") (name "unconnected-(B1-PadD13)") (class "Default")
      (node (ref "B1") (pin "D13") (pinfunction "D13_D13") (pintype "bidirectional"))
    )
    (net (code "86") (name "unconnected-(B1-PadIOREF)") (class "Default")
      (node (ref "B1") (pin "IOREF") (pinfunction "IOREF_IOREF") (pintype "bidirectional"))
    )
    (net (code "87") (name "unconnected-(B1-PadMISO)") (class "Default")
      (node (ref "B1") (pin "MISO") (pinfunction "MISO_MISO") (pintype "bidirectional"))
    )
    (net (code "88") (name "unconnected-(B1-PadMOSI)") (class "Default")
      (node (ref "B1") (pin "MOSI") (pinfunction "MOSI_MOSI") (pintype "bidirectional"))
    )
    (net (code "89") (name "unconnected-(B1-PadSCK)") (class "Default")
      (node (ref "B1") (pin "SCK") (pinfunction "SCK_SCK") (pintype "bidirectional"))
    )
    (net (code "90") (name "unconnected-(B1-PadSCL)") (class "Default")
      (node (ref "B1") (pin "SCL") (pinfunction "SCL_SCL") (pintype "bidirectional"))
    )
    (net (code "91") (name "unconnected-(B1-PadSDA)") (class "Default")
      (node (ref "B1") (pin "SDA") (pinfunction "SDA_SDA") (pintype "bidirectional"))
    )
    (net (code "92") (name "unconnected-(B1-PadVCC)") (class "Default")
      (node (ref "B1") (pin "VCC") (pinfunction "VCC_VCC") (pintype "bidirectional"))
    )
    (net (code "93") (name "unconnected-(B1-~{RESET}-PadRESET@1)") (class "Default")
      (node (ref "B1") (pin "RESET@1") (pinfunction "~{RESET}_RESET@1") (pintype "bidirectional"))
    )
    (net (code "94") (name "unconnected-(IC2-O3-Pad17)") (class "Default")
      (node (ref "IC2") (pin "17") (pinfunction "O3_17") (pintype "output"))
    )
    (net (code "95") (name "unconnected-(IC2-O4-Pad16)") (class "Default")
      (node (ref "IC2") (pin "16") (pinfunction "O4_16") (pintype "output"))
    )
    (net (code "96") (name "unconnected-(IC2-O5-Pad15)") (class "Default")
      (node (ref "IC2") (pin "15") (pinfunction "O5_15") (pintype "output"))
    )
    (net (code "97") (name "unconnected-(IC2-O6-Pad14)") (class "Default")
      (node (ref "IC2") (pin "14") (pinfunction "O6_14") (pintype "output"))
    )
    (net (code "98") (name "unconnected-(IC2-O7-Pad13)") (class "Default")
      (node (ref "IC2") (pin "13") (pinfunction "O7_13") (pintype "output"))
    )
    (net (code "99") (name "unconnected-(IC2-O8-Pad12)") (class "Default")
      (node (ref "IC2") (pin "12") (pinfunction "O8_12") (pintype "output"))
    )
    (net (code "100") (name "unconnected-(IC3A-~{QH}-Pad7)") (class "Default")
      (node (ref "IC3") (pin "7") (pinfunction "~{QH}_7") (pintype "output"))
    )
    (net (code "101") (name "unconnected-(IC4A-~{QH}-Pad7)") (class "Default")
      (node (ref "IC4") (pin "7") (pinfunction "~{QH}_7") (pintype "output"))
    )
    (net (code "102") (name "unconnected-(IC5A-~{QH}-Pad7)") (class "Default")
      (node (ref "IC5") (pin "7") (pinfunction "~{QH}_7") (pintype "output"))
    )
    (net (code "103") (name "unconnected-(IC6A-QH*-Pad9)") (class "Default")
      (node (ref "IC6") (pin "9") (pinfunction "QH*_9") (pintype "tri_state"))
    )
    (net (code "104") (name "unconnected-(J2-Pad3)") (class "Default")
      (node (ref "J2") (pin "3") (pinfunction "3_3") (pintype "passive"))
    )
    (net (code "105") (name "unconnected-(J2-Pad4)") (class "Default")
      (node (ref "J2") (pin "4") (pinfunction "4_4") (pintype "passive"))
    )
    (net (code "106") (name "unconnected-(J2-Pad5)") (class "Default")
      (node (ref "J2") (pin "5") (pinfunction "5_5") (pintype "passive"))
    )
    (net (code "107") (name "unconnected-(J2-Pad6)") (class "Default")
      (node (ref "J2") (pin "6") (pinfunction "6_6") (pintype "passive"))
    )
    (net (code "108") (name "unconnected-(U$1-NC-PadP$39)") (class "Default")
      (node (ref "U$1") (pin "P$39") (pinfunction "NC_P$39") (pintype "bidirectional"))
    )
    (net (code "109") (name "unconnected-(U$1-TEST*-PadP$23)") (class "Default")
      (node (ref "U$1") (pin "P$23") (pinfunction "TEST*_P$23") (pintype "bidirectional"))
    )
  )
)
